# RGB_DMD_MINI.net
KiCad netlist of a schematic drawn in EAGLE
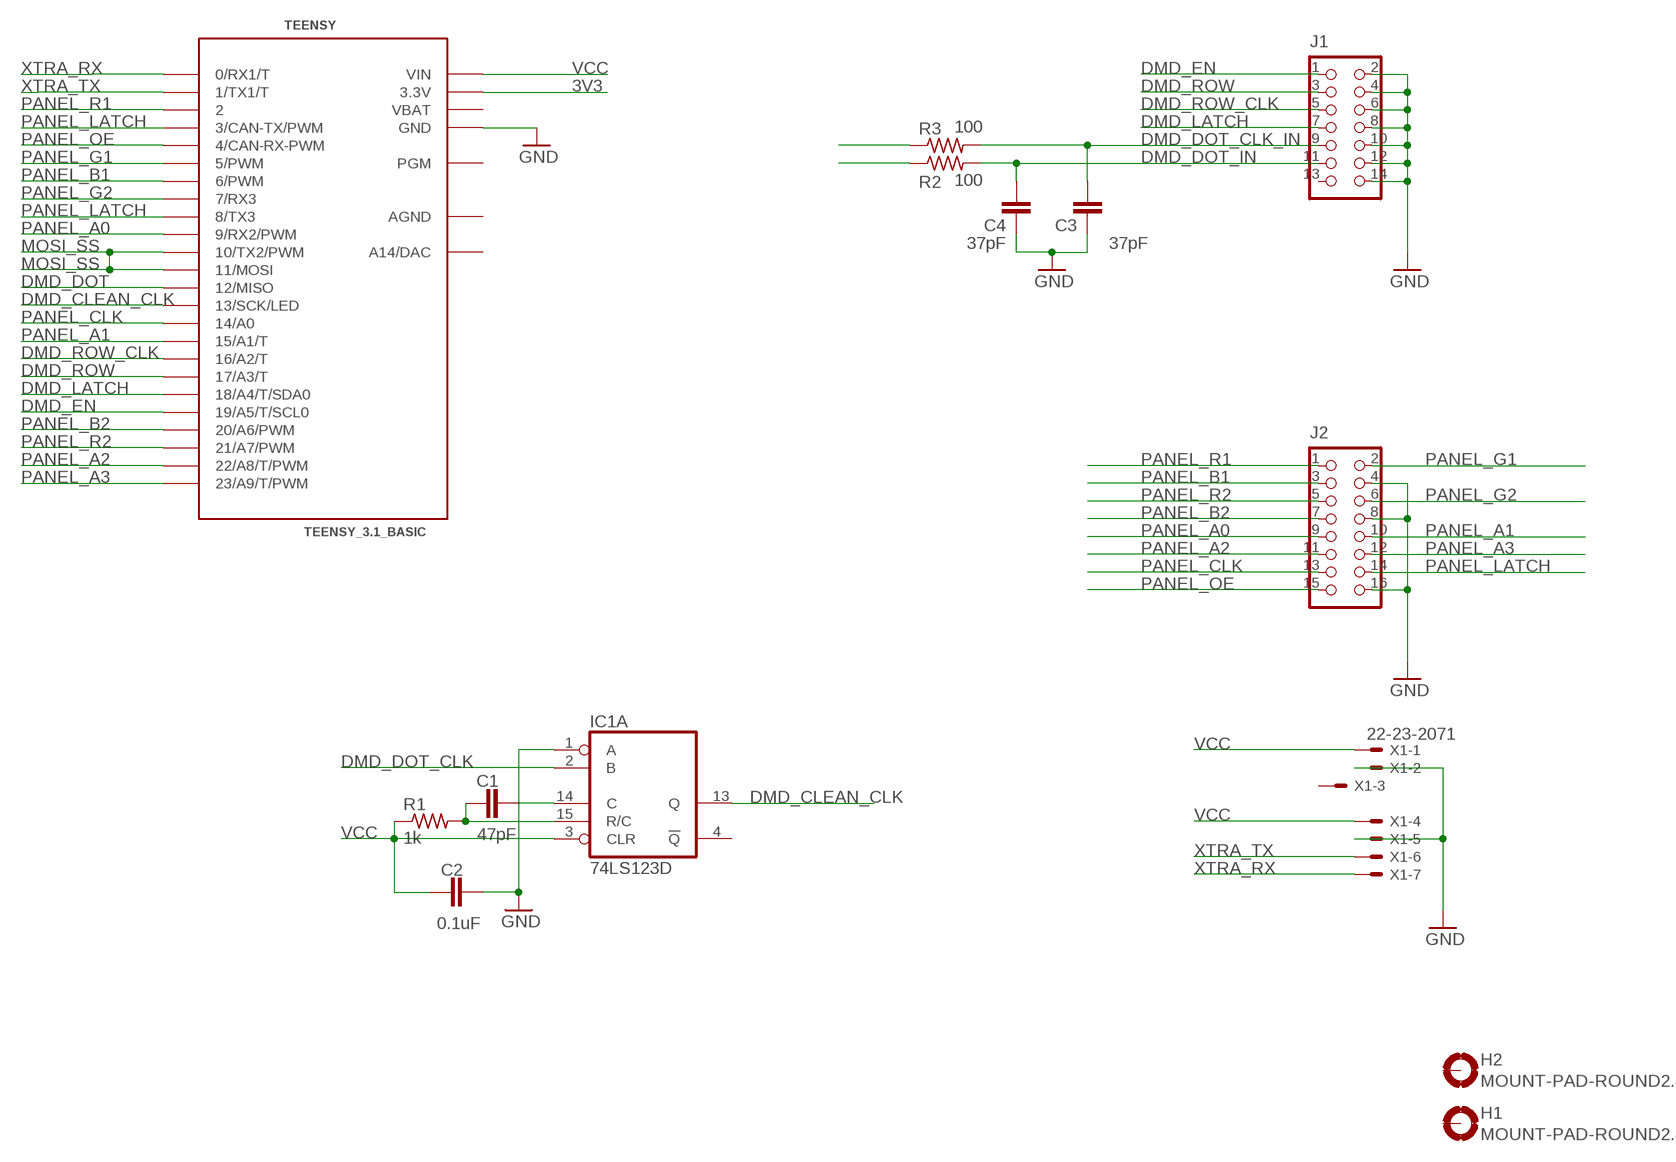
[diagram p0: schematic, sheet 1]

(export (version "E")
  (design (tool "Eeschema 10.0.6"))
  (components
    (comp (ref "C1")
      (value "47pF")
      (footprint "eagle-import:C0603")
      (libsource (lib "eagle-import") (part "C-EUC0603"))
    )
    (comp (ref "C2")
      (value "0.1uF")
      (footprint "eagle-import:C0603")
      (libsource (lib "eagle-import") (part "C-EUC0603"))
    )
    (comp (ref "C3")
      (value "37pF")
      (footprint "eagle-import:C0603")
      (libsource (lib "eagle-import") (part "C-EUC0603"))
    )
    (comp (ref "C4")
      (value "37pF")
      (footprint "eagle-import:C0603")
      (libsource (lib "eagle-import") (part "C-EUC0603"))
    )
    (comp (ref "H1")
      (value "MOUNT-PAD-ROUND2.8")
      (footprint "eagle-import:2,8-PAD")
      (libsource (lib "eagle-import") (part "MOUNT-PAD-ROUND2.8"))
    )
    (comp (ref "H2")
      (value "MOUNT-PAD-ROUND2.8")
      (footprint "eagle-import:2,8-PAD")
      (libsource (lib "eagle-import") (part "MOUNT-PAD-ROUND2.8"))
    )
    (comp (ref "IC1")
      (value "74LS123D")
      (footprint "eagle-import:SO16")
      (libsource (lib "eagle-import") (part "74123DLS"))
    )
    (comp (ref "J1")
      (value "CON_HEADER_2X07-PTH-SHROUDED")
      (footprint "eagle-import:PINSHRD_PTH_2X07")
      (libsource (lib "eagle-import") (part "CON_HEADER_2X07-PTH-SHROUDED"))
    )
    (comp (ref "J2")
      (value "CON_HEADER_2X08-PTH-SHROUDED")
      (footprint "eagle-import:PINSHRD_PTH_2X08")
      (libsource (lib "eagle-import") (part "CON_HEADER_2X08-PTH-SHROUDED"))
    )
    (comp (ref "R1")
      (value "1k")
      (footprint "eagle-import:R0603")
      (libsource (lib "eagle-import") (part "R-US_R0603"))
    )
    (comp (ref "R2")
      (value "100")
      (footprint "eagle-import:R0603")
      (libsource (lib "eagle-import") (part "R-US_R0603"))
    )
    (comp (ref "R3")
      (value "100")
      (footprint "eagle-import:R0603")
      (libsource (lib "eagle-import") (part "R-US_R0603"))
    )
    (comp (ref "TEENSY")
      (value "TEENSY_3.1_BASIC")
      (footprint "eagle-import:TEENSY_3.1_BASIC")
      (libsource (lib "eagle-import") (part "TEENSY_3.1_BASIC"))
    )
    (comp (ref "X1")
      (value "22-23-2071")
      (footprint "eagle-import:22-23-2071")
      (fields (field (name "MF") "MOLEX"))
      (libsource (lib "eagle-import") (part "22-23-2071"))
    )
  )
  (nets
    (net (code "1") (name "/3V3") (class "Default")
      (node (ref "TEENSY") (pin "3.3V") (pinfunction "3.3V_3.3V") (pintype "power_in"))
      (node (ref "TEENSY") (pin "3.3V1") (pinfunction "3.3V_3.3V1") (pintype "power_in"))
    )
    (net (code "2") (name "/AGND") (class "Default")
      (node (ref "TEENSY") (pin "AGND") (pinfunction "AGND_AGND") (pintype "power_in"))
    )
    (net (code "3") (name "/DMD_CLEAN_CLK") (class "Default")
      (node (ref "IC1") (pin "13") (pinfunction "Q_13") (pintype "output"))
      (node (ref "TEENSY") (pin "13") (pinfunction "13/SCK/LED_13") (pintype "bidirectional"))
    )
    (net (code "4") (name "/DMD_DOT") (class "Default")
      (node (ref "R2") (pin "1") (pinfunction "1_1") (pintype "passive"))
      (node (ref "TEENSY") (pin "12") (pinfunction "12/MISO_12") (pintype "bidirectional"))
    )
    (net (code "5") (name "/DMD_DOT_CLK") (class "Default")
      (node (ref "IC1") (pin "2") (pinfunction "B_2") (pintype "input"))
      (node (ref "R3") (pin "1") (pinfunction "1_1") (pintype "passive"))
    )
    (net (code "6") (name "/DMD_DOT_CLK_IN") (class "Default")
      (node (ref "C3") (pin "2") (pinfunction "2_2") (pintype "passive"))
      (node (ref "J1") (pin "9") (pinfunction "9_9") (pintype "passive"))
      (node (ref "R3") (pin "2") (pinfunction "2_2") (pintype "passive"))
    )
    (net (code "7") (name "/DMD_DOT_IN") (class "Default")
      (node (ref "C4") (pin "2") (pinfunction "2_2") (pintype "passive"))
      (node (ref "J1") (pin "11") (pinfunction "11_11") (pintype "passive"))
      (node (ref "R2") (pin "2") (pinfunction "2_2") (pintype "passive"))
    )
    (net (code "8") (name "/DMD_EN") (class "Default")
      (node (ref "J1") (pin "1") (pinfunction "1_1") (pintype "passive"))
      (node (ref "TEENSY") (pin "19/A5") (pinfunction "19/A5/T/SCL0_19/A5") (pintype "bidirectional"))
    )
    (net (code "9") (name "/DMD_LATCH") (class "Default")
      (node (ref "J1") (pin "7") (pinfunction "7_7") (pintype "passive"))
      (node (ref "TEENSY") (pin "18/A4") (pinfunction "18/A4/T/SDA0_18/A4") (pintype "bidirectional"))
    )
    (net (code "10") (name "/DMD_ROW") (class "Default")
      (node (ref "J1") (pin "3") (pinfunction "3_3") (pintype "passive"))
      (node (ref "TEENSY") (pin "17/A3") (pinfunction "17/A3/T_17/A3") (pintype "bidirectional"))
    )
    (net (code "11") (name "/DMD_ROW_CLK") (class "Default")
      (node (ref "J1") (pin "5") (pinfunction "5_5") (pintype "passive"))
      (node (ref "TEENSY") (pin "16/A2") (pinfunction "16/A2/T_16/A2") (pintype "bidirectional"))
    )
    (net (code "12") (name "/MOSI_SS") (class "Default")
      (node (ref "TEENSY") (pin "10") (pinfunction "10/TX2/PWM_10") (pintype "bidirectional"))
      (node (ref "TEENSY") (pin "11") (pinfunction "11/MOSI_11") (pintype "bidirectional"))
    )
    (net (code "13") (name "/PANEL_A0") (class "Default")
      (node (ref "J2") (pin "9") (pinfunction "9_9") (pintype "passive"))
      (node (ref "TEENSY") (pin "9") (pinfunction "9/RX2/PWM_9") (pintype "bidirectional"))
    )
    (net (code "14") (name "/PANEL_A1") (class "Default")
      (node (ref "J2") (pin "10") (pinfunction "10_10") (pintype "passive"))
      (node (ref "TEENSY") (pin "15/A1") (pinfunction "15/A1/T_15/A1") (pintype "bidirectional"))
    )
    (net (code "15") (name "/PANEL_A2") (class "Default")
      (node (ref "J2") (pin "11") (pinfunction "11_11") (pintype "passive"))
      (node (ref "TEENSY") (pin "22/A8") (pinfunction "22/A8/T/PWM_22/A8") (pintype "bidirectional"))
    )
    (net (code "16") (name "/PANEL_A3") (class "Default")
      (node (ref "J2") (pin "12") (pinfunction "12_12") (pintype "passive"))
      (node (ref "TEENSY") (pin "23/A9") (pinfunction "23/A9/T/PWM_23/A9") (pintype "bidirectional"))
    )
    (net (code "17") (name "/PANEL_B1") (class "Default")
      (node (ref "J2") (pin "3") (pinfunction "3_3") (pintype "passive"))
      (node (ref "TEENSY") (pin "6") (pinfunction "6/PWM_6") (pintype "bidirectional"))
    )
    (net (code "18") (name "/PANEL_B2") (class "Default")
      (node (ref "J2") (pin "7") (pinfunction "7_7") (pintype "passive"))
      (node (ref "TEENSY") (pin "20/A6") (pinfunction "20/A6/PWM_20/A6") (pintype "bidirectional"))
    )
    (net (code "19") (name "/PANEL_CLK") (class "Default")
      (node (ref "J2") (pin "13") (pinfunction "13_13") (pintype "passive"))
      (node (ref "TEENSY") (pin "14/A0") (pinfunction "14/A0_14/A0") (pintype "bidirectional"))
    )
    (net (code "20") (name "/PANEL_G1") (class "Default")
      (node (ref "J2") (pin "2") (pinfunction "2_2") (pintype "passive"))
      (node (ref "TEENSY") (pin "5") (pinfunction "5/PWM_5") (pintype "bidirectional"))
    )
    (net (code "21") (name "/PANEL_G2") (class "Default")
      (node (ref "J2") (pin "6") (pinfunction "6_6") (pintype "passive"))
      (node (ref "TEENSY") (pin "7") (pinfunction "7/RX3_7") (pintype "bidirectional"))
    )
    (net (code "22") (name "/PANEL_LATCH") (class "Default")
      (node (ref "J2") (pin "14") (pinfunction "14_14") (pintype "passive"))
      (node (ref "TEENSY") (pin "3") (pinfunction "3/CAN-TX/PWM_3") (pintype "bidirectional"))
      (node (ref "TEENSY") (pin "8") (pinfunction "8/TX3_8") (pintype "bidirectional"))
    )
    (net (code "23") (name "/PANEL_OE") (class "Default")
      (node (ref "J2") (pin "15") (pinfunction "15_15") (pintype "passive"))
      (node (ref "TEENSY") (pin "4") (pinfunction "4/CAN-RX-PWM_4") (pintype "bidirectional"))
    )
    (net (code "24") (name "/PANEL_R1") (class "Default")
      (node (ref "J2") (pin "1") (pinfunction "1_1") (pintype "passive"))
      (node (ref "TEENSY") (pin "2") (pinfunction "2_2") (pintype "bidirectional"))
    )
    (net (code "25") (name "/PANEL_R2") (class "Default")
      (node (ref "J2") (pin "5") (pinfunction "5_5") (pintype "passive"))
      (node (ref "TEENSY") (pin "21/A7") (pinfunction "21/A7/PWM_21/A7") (pintype "bidirectional"))
    )
    (net (code "26") (name "/VBAT") (class "Default")
      (node (ref "TEENSY") (pin "VBAT") (pinfunction "VBAT_VBAT") (pintype "power_in"))
    )
    (net (code "27") (name "/VCC") (class "Default")
      (node (ref "C2") (pin "1") (pinfunction "1_1") (pintype "passive"))
      (node (ref "IC1") (pin "3") (pinfunction "CLR_3") (pintype "input"))
      (node (ref "R1") (pin "1") (pinfunction "1_1") (pintype "passive"))
      (node (ref "TEENSY") (pin "VIN") (pinfunction "VIN_VIN") (pintype "power_in"))
      (node (ref "X1") (pin "1") (pinfunction "S_1") (pintype "passive"))
      (node (ref "X1") (pin "4") (pinfunction "S_4") (pintype "passive"))
    )
    (net (code "28") (name "/XTRA_RX") (class "Default")
      (node (ref "TEENSY") (pin "0") (pinfunction "0/RX1/T_0") (pintype "bidirectional"))
      (node (ref "X1") (pin "7") (pinfunction "S_7") (pintype "passive"))
    )
    (net (code "29") (name "/XTRA_TX") (class "Default")
      (node (ref "TEENSY") (pin "1") (pinfunction "1/TX1/T_1") (pintype "bidirectional"))
      (node (ref "X1") (pin "6") (pinfunction "S_6") (pintype "passive"))
    )
    (net (code "30") (name "GND") (class "Default")
      (node (ref "C2") (pin "2") (pinfunction "2_2") (pintype "passive"))
      (node (ref "C3") (pin "1") (pinfunction "1_1") (pintype "passive"))
      (node (ref "C4") (pin "1") (pinfunction "1_1") (pintype "passive"))
      (node (ref "IC1") (pin "1") (pinfunction "A_1") (pintype "input"))
      (node (ref "J1") (pin "10") (pinfunction "10_10") (pintype "passive"))
      (node (ref "J1") (pin "12") (pinfunction "12_12") (pintype "passive"))
      (node (ref "J1") (pin "14") (pinfunction "14_14") (pintype "passive"))
      (node (ref "J1") (pin "2") (pinfunction "2_2") (pintype "passive"))
      (node (ref "J1") (pin "4") (pinfunction "4_4") (pintype "passive"))
      (node (ref "J1") (pin "6") (pinfunction "6_6") (pintype "passive"))
      (node (ref "J1") (pin "8") (pinfunction "8_8") (pintype "passive"))
      (node (ref "J2") (pin "16") (pinfunction "16_16") (pintype "passive"))
      (node (ref "J2") (pin "4") (pinfunction "4_4") (pintype "passive"))
      (node (ref "J2") (pin "8") (pinfunction "8_8") (pintype "passive"))
      (node (ref "TEENSY") (pin "GND") (pinfunction "GND_GND") (pintype "power_in"))
      (node (ref "TEENSY") (pin "GND1") (pinfunction "GND_GND1") (pintype "power_in"))
      (node (ref "X1") (pin "2") (pinfunction "S_2") (pintype "passive"))
      (node (ref "X1") (pin "5") (pinfunction "S_5") (pintype "passive"))
    )
    (net (code "31") (name "Net-(IC1A-C)") (class "Default")
      (node (ref "C1") (pin "2") (pinfunction "2_2") (pintype "passive"))
      (node (ref "IC1") (pin "14") (pinfunction "C_14") (pintype "input"))
    )
    (net (code "32") (name "Net-(IC1A-R{slash}C)") (class "Default")
      (node (ref "C1") (pin "1") (pinfunction "1_1") (pintype "passive"))
      (node (ref "IC1") (pin "15") (pinfunction "R/C_15") (pintype "input"))
      (node (ref "R1") (pin "2") (pinfunction "2_2") (pintype "passive"))
    )
    (net (code "33") (name "unconnected-(H1-MOUNT-PadB2,8)") (class "Default")
      (node (ref "H1") (pin "B2,8") (pinfunction "MOUNT_B2,8") (pintype "passive"))
    )
    (net (code "34") (name "unconnected-(H2-MOUNT-PadB2,8)") (class "Default")
      (node (ref "H2") (pin "B2,8") (pinfunction "MOUNT_B2,8") (pintype "passive"))
    )
    (net (code "35") (name "unconnected-(IC1A-~{Q}-Pad4)") (class "Default")
      (node (ref "IC1") (pin "4") (pinfunction "~{Q}_4") (pintype "output"))
    )
    (net (code "36") (name "unconnected-(J1-Pad13)") (class "Default")
      (node (ref "J1") (pin "13") (pinfunction "13_13") (pintype "passive"))
    )
    (net (code "37") (name "unconnected-(TEENSY-A14{slash}DAC-PadA14)") (class "Default")
      (node (ref "TEENSY") (pin "A14") (pinfunction "A14/DAC_A14") (pintype "bidirectional"))
    )
    (net (code "38") (name "unconnected-(TEENSY-PadPGM)") (class "Default")
      (node (ref "TEENSY") (pin "PGM") (pinfunction "PGM_PGM") (pintype "bidirectional"))
    )
    (net (code "39") (name "unconnected-(X1C-S-Pad3)") (class "Default")
      (node (ref "X1") (pin "3") (pinfunction "S_3") (pintype "passive"))
    )
  )
)
